# Sheet1.net
KiCad netlist of a schematic drawn in Altium Designer
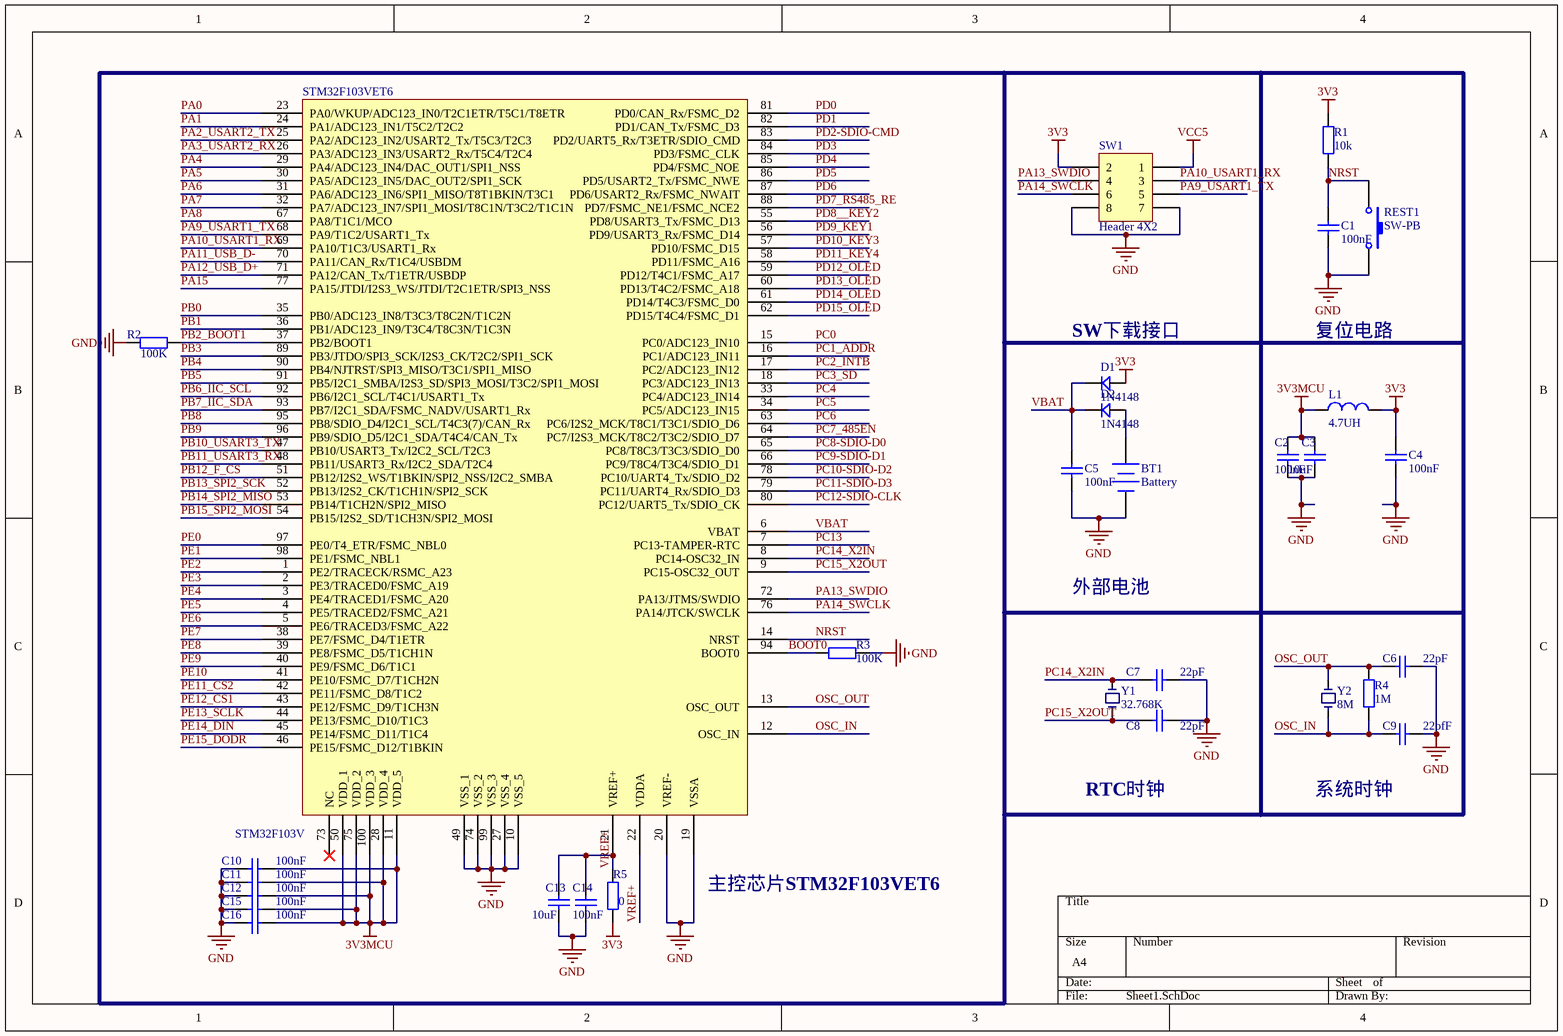
[diagram p0: Sheet1.SchDoc]

(export (version "E")
  (design (tool "Eeschema 10.0.6"))
  (components
    (comp (ref "BT1")
      (value "Battery")
      (footprint "BATTERY_CR1220")
      (description "备份电池")
      (fields (field (name "PUBLISHER") "Altium Limited"))
      (libsource (lib "liu_2016") (part "Battery"))
    )
    (comp (ref "C1")
      (value "100nF")
      (footprint "LC-0603_C")
      (description "无极性电容")
      (fields (field (name "PUBLISHER") "Altium Limited"))
      (libsource (lib "liu_2016") (part "Cap"))
    )
    (comp (ref "C2")
      (value "100nF")
      (footprint "LC-0603_C")
      (description "无极性电容")
      (fields (field (name "PUBLISHER") "Altium Limited"))
      (libsource (lib "liu_2016") (part "Cap"))
    )
    (comp (ref "C3")
      (value "10uF")
      (footprint "LC-0805_C")
      (description "贴片电容")
      (libsource (lib "Miscellaneous Devices LC") (part "0805 1.0pF (010) 0.25pF 50V"))
    )
    (comp (ref "C4")
      (value "100nF")
      (footprint "LC-0603_C")
      (description "无极性电容")
      (fields (field (name "PUBLISHER") "Altium Limited"))
      (libsource (lib "liu_2016") (part "Cap"))
    )
    (comp (ref "C5")
      (value "100nF")
      (footprint "LC-0603_C")
      (description "无极性电容")
      (fields (field (name "PUBLISHER") "Altium Limited"))
      (libsource (lib "liu_2016") (part "Cap"))
    )
    (comp (ref "C6")
      (value "22pF")
      (footprint "LC-0603_C")
      (description "无极性电容")
      (fields (field (name "PUBLISHER") "Altium Limited"))
      (libsource (lib "liu_2016") (part "Cap"))
    )
    (comp (ref "C7")
      (value "22pF")
      (footprint "LC-0603_C")
      (description "无极性电容")
      (fields (field (name "PUBLISHER") "Altium Limited"))
      (libsource (lib "liu_2016") (part "Cap"))
    )
    (comp (ref "C8")
      (value "22pF")
      (footprint "LC-0603_C")
      (description "无极性电容")
      (fields (field (name "PUBLISHER") "Altium Limited"))
      (libsource (lib "liu_2016") (part "Cap"))
    )
    (comp (ref "C9")
      (value "22pfF")
      (footprint "LC-0603_C")
      (description "无极性电容")
      (fields (field (name "PUBLISHER") "Altium Limited"))
      (libsource (lib "liu_2016") (part "Cap"))
    )
    (comp (ref "C10")
      (value "100nF")
      (footprint "LC-0603_C")
      (description "无极性电容")
      (fields (field (name "PUBLISHER") "Altium Limited"))
      (libsource (lib "liu_2016") (part "Cap"))
    )
    (comp (ref "C11")
      (value "100nF")
      (footprint "LC-0603_C")
      (description "无极性电容")
      (fields (field (name "PUBLISHER") "Altium Limited"))
      (libsource (lib "liu_2016") (part "Cap"))
    )
    (comp (ref "C12")
      (value "100nF")
      (footprint "LC-0603_C")
      (description "无极性电容")
      (fields (field (name "PUBLISHER") "Altium Limited"))
      (libsource (lib "liu_2016") (part "Cap"))
    )
    (comp (ref "C13")
      (value "10uF")
      (footprint "LC-0805_C")
      (description "贴片电容")
      (libsource (lib "Miscellaneous Devices LC") (part "0805 1.0pF (010) 0.25pF 50V"))
    )
    (comp (ref "C14")
      (value "100nF")
      (footprint "LC-0603_C")
      (description "无极性电容")
      (fields (field (name "PUBLISHER") "Altium Limited"))
      (libsource (lib "liu_2016") (part "Cap"))
    )
    (comp (ref "C15")
      (value "100nF")
      (footprint "LC-0603_C")
      (description "无极性电容")
      (fields (field (name "PUBLISHER") "Altium Limited"))
      (libsource (lib "liu_2016") (part "Cap"))
    )
    (comp (ref "C16")
      (value "100nF")
      (footprint "LC-0603_C")
      (description "无极性电容")
      (fields (field (name "PUBLISHER") "Altium Limited"))
      (libsource (lib "liu_2016") (part "Cap"))
    )
    (comp (ref "D1")
      (value "1N4148")
      (footprint "DIODE_SOP")
      (libsource (lib "Explorer STM32F407封装库") (part "D"))
    )
    (comp (ref "D2")
      (value "1N4148")
      (footprint "DIODE_SOP")
      (libsource (lib "Explorer STM32F407封装库") (part "D"))
    )
    (comp (ref "L1") (value "4.7UH") (footprint "LC-0805_L") (libsource (lib "liulei") (part "电感")))
    (comp (ref "R1")
      (value "10k")
      (footprint "LC-0603_R")
      (description "贴片电阻")
      (fields (field (name "PUBLISHER") "Altium Limited"))
      (libsource (lib "liu_2016") (part "Res1"))
    )
    (comp (ref "R2")
      (value "100K")
      (footprint "LC-0603_R")
      (description "贴片电阻")
      (fields (field (name "PUBLISHER") "Altium Limited"))
      (libsource (lib "") (part "Res1_2"))
    )
    (comp (ref "R3")
      (value "100K")
      (footprint "LC-0603_R")
      (description "贴片电阻")
      (fields (field (name "PUBLISHER") "Altium Limited"))
      (libsource (lib "") (part "Res1_2"))
    )
    (comp (ref "R4")
      (value "1M")
      (footprint "LC-0603_R")
      (description "贴片电阻")
      (fields (field (name "PUBLISHER") "Altium Limited"))
      (libsource (lib "") (part "Res1_1"))
    )
    (comp (ref "R5")
      (value "0")
      (footprint "LC-0603_R")
      (description "贴片电阻")
      (fields (field (name "PUBLISHER") "Altium Limited"))
      (libsource (lib "") (part "Res1_1"))
    )
    (comp (ref "REST1")
      (value "SW-PB")
      (footprint "SW-SMD1")
      (description "Switch")
      (fields (field (name "PUBLISHER") "Altium Limited"))
      (libsource (lib "PCB_Project") (part "SW-PB"))
    )
    (comp (ref "STM32F103VET6")
      (value "STM32F103V")
      (footprint "LQFP-100_M")
      (description "STM32单片机100引脚")
      (libsource (lib "liu_2016") (part "STM32F103V"))
    )
    (comp (ref "SW1")
      (value "Header 4X2")
      (footprint "HDR2X4")
      (description "Header, 4-Pin, Dual row")
      (fields (field (name "PUBLISHER") "Altium Limited"))
      (libsource (lib "Sparks") (part "Header 4X2"))
    )
    (comp (ref "Y1") (value "32.768K") (footprint "XTAL-长形 贴片") (libsource (lib "liulei") (part "晶振")))
    (comp (ref "Y2") (value "8M") (footprint "XTAL 直插") (libsource (lib "liulei") (part "晶振")))
  )
  (nets
    (net (code "1") (name "/BOOT0") (class "Default")
      (node (ref "R3") (pin "2") (pinfunction "2_2") (pintype "passive"))
      (node (ref "STM32F103VET6") (pin "94") (pinfunction "BOOT0_94") (pintype "passive"))
    )
    (net (code "2") (name "/NRST") (class "Default")
      (node (ref "C1") (pin "1") (pinfunction "1_1") (pintype "passive"))
      (node (ref "R1") (pin "2") (pinfunction "2_2") (pintype "passive"))
      (node (ref "REST1") (pin "1") (pinfunction "1_1") (pintype "passive"))
      (node (ref "STM32F103VET6") (pin "14") (pinfunction "NRST_14") (pintype "passive"))
    )
    (net (code "3") (name "/OSC_IN") (class "Default")
      (node (ref "C9") (pin "1") (pinfunction "1_1") (pintype "passive"))
      (node (ref "R4") (pin "1") (pinfunction "1_1") (pintype "passive"))
      (node (ref "STM32F103VET6") (pin "12") (pinfunction "OSC_IN_12") (pintype "passive"))
      (node (ref "Y2") (pin "1") (pinfunction "1_1") (pintype "passive"))
    )
    (net (code "4") (name "/OSC_OUT") (class "Default")
      (node (ref "C6") (pin "1") (pinfunction "1_1") (pintype "passive"))
      (node (ref "R4") (pin "2") (pinfunction "2_2") (pintype "passive"))
      (node (ref "STM32F103VET6") (pin "13") (pinfunction "OSC_OUT_13") (pintype "passive"))
      (node (ref "Y2") (pin "2") (pinfunction "2_2") (pintype "passive"))
    )
    (net (code "5") (name "/PA0") (class "Default")
      (node (ref "STM32F103VET6") (pin "23") (pinfunction "PA0/WKUP/ADC123_IN0/T2C1ETR/T5C1/T8ETR_23") (pintype "passive"))
    )
    (net (code "6") (name "/PA1") (class "Default")
      (node (ref "STM32F103VET6") (pin "24") (pinfunction "PA1/ADC123_IN1/T5C2/T2C2_24") (pintype "passive"))
    )
    (net (code "7") (name "/PA2_USART2_TX") (class "Default")
      (node (ref "STM32F103VET6") (pin "25") (pinfunction "PA2/ADC123_IN2/USART2_Tx/T5C3/T2C3_25") (pintype "passive"))
    )
    (net (code "8") (name "/PA3_USART2_RX") (class "Default")
      (node (ref "STM32F103VET6") (pin "26") (pinfunction "PA3/ADC123_IN3/USART2_Rx/T5C4/T2C4_26") (pintype "passive"))
    )
    (net (code "9") (name "/PA4") (class "Default")
      (node (ref "STM32F103VET6") (pin "29") (pinfunction "PA4/ADC123_IN4/DAC_OUT1/SPI1_NSS_29") (pintype "passive"))
    )
    (net (code "10") (name "/PA5") (class "Default")
      (node (ref "STM32F103VET6") (pin "30") (pinfunction "PA5/ADC123_IN5/DAC_OUT2/SPI1_SCK_30") (pintype "passive"))
    )
    (net (code "11") (name "/PA6") (class "Default")
      (node (ref "STM32F103VET6") (pin "31") (pinfunction "PA6/ADC123_IN6/SPI1_MISO/T8T1BKIN/T3C1_31") (pintype "passive"))
    )
    (net (code "12") (name "/PA7") (class "Default")
      (node (ref "STM32F103VET6") (pin "32") (pinfunction "PA7/ADC123_IN7/SPI1_MOSI/T8C1N/T3C2/T1C1N_32") (pintype "passive"))
    )
    (net (code "13") (name "/PA8") (class "Default")
      (node (ref "STM32F103VET6") (pin "67") (pinfunction "PA8/T1C1/MCO_67") (pintype "passive"))
    )
    (net (code "14") (name "/PA9_USART1_TX") (class "Default")
      (node (ref "STM32F103VET6") (pin "68") (pinfunction "PA9/T1C2/USART1_Tx_68") (pintype "passive"))
      (node (ref "SW1") (pin "5") (pinfunction "5_5") (pintype "passive"))
    )
    (net (code "15") (name "/PA10_USART1_RX") (class "Default")
      (node (ref "STM32F103VET6") (pin "69") (pinfunction "PA10/T1C3/USART1_Rx_69") (pintype "passive"))
      (node (ref "SW1") (pin "3") (pinfunction "3_3") (pintype "passive"))
    )
    (net (code "16") (name "/PA11_USB_D-") (class "Default")
      (node (ref "STM32F103VET6") (pin "70") (pinfunction "PA11/CAN_Rx/T1C4/USBDM_70") (pintype "passive"))
    )
    (net (code "17") (name "/PA12_USB_D+") (class "Default")
      (node (ref "STM32F103VET6") (pin "71") (pinfunction "PA12/CAN_Tx/T1ETR/USBDP_71") (pintype "passive"))
    )
    (net (code "18") (name "/PA13_SWDIO") (class "Default")
      (node (ref "STM32F103VET6") (pin "72") (pinfunction "PA13/JTMS/SWDIO_72") (pintype "passive"))
      (node (ref "SW1") (pin "4") (pinfunction "4_4") (pintype "passive"))
    )
    (net (code "19") (name "/PA14_SWCLK") (class "Default")
      (node (ref "STM32F103VET6") (pin "76") (pinfunction "PA14/JTCK/SWCLK_76") (pintype "passive"))
      (node (ref "SW1") (pin "6") (pinfunction "6_6") (pintype "passive"))
    )
    (net (code "20") (name "/PA15") (class "Default")
      (node (ref "STM32F103VET6") (pin "77") (pinfunction "PA15/JTDI/I2S3_WS/JTDI/T2C1ETR/SPI3_NSS_77") (pintype "passive"))
    )
    (net (code "21") (name "/PB0") (class "Default")
      (node (ref "STM32F103VET6") (pin "35") (pinfunction "PB0/ADC123_IN8/T3C3/T8C2N/T1C2N_35") (pintype "passive"))
    )
    (net (code "22") (name "/PB1") (class "Default")
      (node (ref "STM32F103VET6") (pin "36") (pinfunction "PB1/ADC123_IN9/T3C4/T8C3N/T1C3N_36") (pintype "passive"))
    )
    (net (code "23") (name "/PB2_BOOT1") (class "Default")
      (node (ref "R2") (pin "1") (pinfunction "1_1") (pintype "passive"))
      (node (ref "STM32F103VET6") (pin "37") (pinfunction "PB2/BOOT1_37") (pintype "passive"))
    )
    (net (code "24") (name "/PB3") (class "Default")
      (node (ref "STM32F103VET6") (pin "89") (pinfunction "PB3/JTDO/SPI3_SCK/I2S3_CK/T2C2/SPI1_SCK_89") (pintype "passive"))
    )
    (net (code "25") (name "/PB4") (class "Default")
      (node (ref "STM32F103VET6") (pin "90") (pinfunction "PB4/NJTRST/SPI3_MISO/T3C1/SPI1_MISO_90") (pintype "passive"))
    )
    (net (code "26") (name "/PB5") (class "Default")
      (node (ref "STM32F103VET6") (pin "91") (pinfunction "PB5/I2C1_SMBA/I2S3_SD/SPI3_MOSI/T3C2/SPI1_MOSI_91") (pintype "passive"))
    )
    (net (code "27") (name "/PB6_IIC_SCL") (class "Default")
      (node (ref "STM32F103VET6") (pin "92") (pinfunction "PB6/I2C1_SCL/T4C1/USART1_Tx_92") (pintype "passive"))
    )
    (net (code "28") (name "/PB7_IIC_SDA") (class "Default")
      (node (ref "STM32F103VET6") (pin "93") (pinfunction "PB7/I2C1_SDA/FSMC_NADV/USART1_Rx_93") (pintype "passive"))
    )
    (net (code "29") (name "/PB8") (class "Default")
      (node (ref "STM32F103VET6") (pin "95") (pinfunction "PB8/SDIO_D4/I2C1_SCL/T4C3(7)/CAN_Rx_95") (pintype "passive"))
    )
    (net (code "30") (name "/PB9") (class "Default")
      (node (ref "STM32F103VET6") (pin "96") (pinfunction "PB9/SDIO_D5/I2C1_SDA/T4C4/CAN_Tx_96") (pintype "passive"))
    )
    (net (code "31") (name "/PB10_USART3_TX") (class "Default")
      (node (ref "STM32F103VET6") (pin "47") (pinfunction "PB10/USART3_Tx/I2C2_SCL/T2C3_47") (pintype "passive"))
    )
    (net (code "32") (name "/PB11_USART3_RX") (class "Default")
      (node (ref "STM32F103VET6") (pin "48") (pinfunction "PB11/USART3_Rx/I2C2_SDA/T2C4_48") (pintype "passive"))
    )
    (net (code "33") (name "/PB12_F_CS") (class "Default")
      (node (ref "STM32F103VET6") (pin "51") (pinfunction "PB12/I2S2_WS/T1BKIN/SPI2_NSS/I2C2_SMBA_51") (pintype "passive"))
    )
    (net (code "34") (name "/PB13_SPI2_SCK") (class "Default")
      (node (ref "STM32F103VET6") (pin "52") (pinfunction "PB13/I2S2_CK/T1CH1N/SPI2_SCK_52") (pintype "passive"))
    )
    (net (code "35") (name "/PB14_SPI2_MISO") (class "Default")
      (node (ref "STM32F103VET6") (pin "53") (pinfunction "PB14/T1CH2N/SPI2_MISO_53") (pintype "passive"))
    )
    (net (code "36") (name "/PB15_SPI2_MOSI") (class "Default")
      (node (ref "STM32F103VET6") (pin "54") (pinfunction "PB15/I2S2_SD/T1CH3N/SPI2_MOSI_54") (pintype "passive"))
    )
    (net (code "37") (name "/PC0") (class "Default")
      (node (ref "STM32F103VET6") (pin "15") (pinfunction "PC0/ADC123_IN10_15") (pintype "passive"))
    )
    (net (code "38") (name "/PC1_ADDR") (class "Default")
      (node (ref "STM32F103VET6") (pin "16") (pinfunction "PC1/ADC123_IN11_16") (pintype "passive"))
    )
    (net (code "39") (name "/PC2_INTB") (class "Default")
      (node (ref "STM32F103VET6") (pin "17") (pinfunction "PC2/ADC123_IN12_17") (pintype "passive"))
    )
    (net (code "40") (name "/PC3_SD") (class "Default")
      (node (ref "STM32F103VET6") (pin "18") (pinfunction "PC3/ADC123_IN13_18") (pintype "passive"))
    )
    (net (code "41") (name "/PC4") (class "Default")
      (node (ref "STM32F103VET6") (pin "33") (pinfunction "PC4/ADC123_IN14_33") (pintype "passive"))
    )
    (net (code "42") (name "/PC5") (class "Default")
      (node (ref "STM32F103VET6") (pin "34") (pinfunction "PC5/ADC123_IN15_34") (pintype "passive"))
    )
    (net (code "43") (name "/PC6") (class "Default")
      (node (ref "STM32F103VET6") (pin "63") (pinfunction "PC6/I2S2_MCK/T8C1/T3C1/SDIO_D6_63") (pintype "passive"))
    )
    (net (code "44") (name "/PC7_485EN") (class "Default")
      (node (ref "STM32F103VET6") (pin "64") (pinfunction "PC7/I2S3_MCK/T8C2/T3C2/SDIO_D7_64") (pintype "passive"))
    )
    (net (code "45") (name "/PC8-SDIO-D0") (class "Default")
      (node (ref "STM32F103VET6") (pin "65") (pinfunction "PC8/T8C3/T3C3/SDIO_D0_65") (pintype "passive"))
    )
    (net (code "46") (name "/PC9-SDIO-D1") (class "Default")
      (node (ref "STM32F103VET6") (pin "66") (pinfunction "PC9/T8C4/T3C4/SDIO_D1_66") (pintype "passive"))
    )
    (net (code "47") (name "/PC10-SDIO-D2") (class "Default")
      (node (ref "STM32F103VET6") (pin "78") (pinfunction "PC10/UART4_Tx/SDIO_D2_78") (pintype "passive"))
    )
    (net (code "48") (name "/PC11-SDIO-D3") (class "Default")
      (node (ref "STM32F103VET6") (pin "79") (pinfunction "PC11/UART4_Rx/SDIO_D3_79") (pintype "passive"))
    )
    (net (code "49") (name "/PC12-SDIO-CLK") (class "Default")
      (node (ref "STM32F103VET6") (pin "80") (pinfunction "PC12/UART5_Tx/SDIO_CK_80") (pintype "passive"))
    )
    (net (code "50") (name "/PC13") (class "Default")
      (node (ref "STM32F103VET6") (pin "7") (pinfunction "PC13-TAMPER-RTC_7") (pintype "passive"))
    )
    (net (code "51") (name "/PC14_X2IN") (class "Default")
      (node (ref "C7") (pin "1") (pinfunction "1_1") (pintype "passive"))
      (node (ref "STM32F103VET6") (pin "8") (pinfunction "PC14-OSC32_IN_8") (pintype "passive"))
      (node (ref "Y1") (pin "2") (pinfunction "2_2") (pintype "passive"))
    )
    (net (code "52") (name "/PC15_X2OUT") (class "Default")
      (node (ref "C8") (pin "1") (pinfunction "1_1") (pintype "passive"))
      (node (ref "STM32F103VET6") (pin "9") (pinfunction "PC15-OSC32_OUT_9") (pintype "passive"))
      (node (ref "Y1") (pin "1") (pinfunction "1_1") (pintype "passive"))
    )
    (net (code "53") (name "/PD0") (class "Default")
      (node (ref "STM32F103VET6") (pin "81") (pinfunction "PD0/CAN_Rx/FSMC_D2_81") (pintype "passive"))
    )
    (net (code "54") (name "/PD1") (class "Default")
      (node (ref "STM32F103VET6") (pin "82") (pinfunction "PD1/CAN_Tx/FSMC_D3_82") (pintype "passive"))
    )
    (net (code "55") (name "/PD2-SDIO-CMD") (class "Default")
      (node (ref "STM32F103VET6") (pin "83") (pinfunction "PD2/UART5_Rx/T3ETR/SDIO_CMD_83") (pintype "passive"))
    )
    (net (code "56") (name "/PD3") (class "Default")
      (node (ref "STM32F103VET6") (pin "84") (pinfunction "PD3/FSMC_CLK_84") (pintype "passive"))
    )
    (net (code "57") (name "/PD4") (class "Default")
      (node (ref "STM32F103VET6") (pin "85") (pinfunction "PD4/FSMC_NOE_85") (pintype "passive"))
    )
    (net (code "58") (name "/PD5") (class "Default")
      (node (ref "STM32F103VET6") (pin "86") (pinfunction "PD5/USART2_Tx/FSMC_NWE_86") (pintype "passive"))
    )
    (net (code "59") (name "/PD6") (class "Default")
      (node (ref "STM32F103VET6") (pin "87") (pinfunction "PD6/USART2_Rx/FSMC_NWAIT_87") (pintype "passive"))
    )
    (net (code "60") (name "/PD7_RS485_RE") (class "Default")
      (node (ref "STM32F103VET6") (pin "88") (pinfunction "PD7/FSMC_NE1/FSMC_NCE2_88") (pintype "passive"))
    )
    (net (code "61") (name "/PD8__KEY2") (class "Default")
      (node (ref "STM32F103VET6") (pin "55") (pinfunction "PD8/USART3_Tx/FSMC_D13_55") (pintype "passive"))
    )
    (net (code "62") (name "/PD9_KEY1") (class "Default")
      (node (ref "STM32F103VET6") (pin "56") (pinfunction "PD9/USART3_Rx/FSMC_D14_56") (pintype "passive"))
    )
    (net (code "63") (name "/PD10_KEY3") (class "Default")
      (node (ref "STM32F103VET6") (pin "57") (pinfunction "PD10/FSMC_D15_57") (pintype "passive"))
    )
    (net (code "64") (name "/PD11_KEY4") (class "Default")
      (node (ref "STM32F103VET6") (pin "58") (pinfunction "PD11/FSMC_A16_58") (pintype "passive"))
    )
    (net (code "65") (name "/PD12_OLED") (class "Default")
      (node (ref "STM32F103VET6") (pin "59") (pinfunction "PD12/T4C1/FSMC_A17_59") (pintype "passive"))
    )
    (net (code "66") (name "/PD13_OLED") (class "Default")
      (node (ref "STM32F103VET6") (pin "60") (pinfunction "PD13/T4C2/FSMC_A18_60") (pintype "passive"))
    )
    (net (code "67") (name "/PD14_OLED") (class "Default")
      (node (ref "STM32F103VET6") (pin "61") (pinfunction "PD14/T4C3/FSMC_D0_61") (pintype "passive"))
    )
    (net (code "68") (name "/PD15_OLED") (class "Default")
      (node (ref "STM32F103VET6") (pin "62") (pinfunction "PD15/T4C4/FSMC_D1_62") (pintype "passive"))
    )
    (net (code "69") (name "/PE0") (class "Default")
      (node (ref "STM32F103VET6") (pin "97") (pinfunction "PE0/T4_ETR/FSMC_NBL0_97") (pintype "passive"))
    )
    (net (code "70") (name "/PE1") (class "Default")
      (node (ref "STM32F103VET6") (pin "98") (pinfunction "PE1/FSMC_NBL1_98") (pintype "passive"))
    )
    (net (code "71") (name "/PE2") (class "Default")
      (node (ref "STM32F103VET6") (pin "1") (pinfunction "PE2/TRACECK/RSMC_A23_1") (pintype "passive"))
    )
    (net (code "72") (name "/PE3") (class "Default")
      (node (ref "STM32F103VET6") (pin "2") (pinfunction "PE3/TRACED0/FSMC_A19_2") (pintype "passive"))
    )
    (net (code "73") (name "/PE4") (class "Default")
      (node (ref "STM32F103VET6") (pin "3") (pinfunction "PE4/TRACED1/FSMC_A20_3") (pintype "passive"))
    )
    (net (code "74") (name "/PE5") (class "Default")
      (node (ref "STM32F103VET6") (pin "4") (pinfunction "PE5/TRACED2/FSMC_A21_4") (pintype "passive"))
    )
    (net (code "75") (name "/PE6") (class "Default")
      (node (ref "STM32F103VET6") (pin "5") (pinfunction "PE6/TRACED3/FSMC_A22_5") (pintype "passive"))
    )
    (net (code "76") (name "/PE7") (class "Default")
      (node (ref "STM32F103VET6") (pin "38") (pinfunction "PE7/FSMC_D4/T1ETR_38") (pintype "passive"))
    )
    (net (code "77") (name "/PE8") (class "Default")
      (node (ref "STM32F103VET6") (pin "39") (pinfunction "PE8/FSMC_D5/T1CH1N_39") (pintype "passive"))
    )
    (net (code "78") (name "/PE9") (class "Default")
      (node (ref "STM32F103VET6") (pin "40") (pinfunction "PE9/FSMC_D6/T1C1_40") (pintype "passive"))
    )
    (net (code "79") (name "/PE10") (class "Default")
      (node (ref "STM32F103VET6") (pin "41") (pinfunction "PE10/FSMC_D7/T1CH2N_41") (pintype "passive"))
    )
    (net (code "80") (name "/PE11_CS2") (class "Default")
      (node (ref "STM32F103VET6") (pin "42") (pinfunction "PE11/FSMC_D8/T1C2_42") (pintype "passive"))
    )
    (net (code "81") (name "/PE12_CS1") (class "Default")
      (node (ref "STM32F103VET6") (pin "43") (pinfunction "PE12/FSMC_D9/T1CH3N_43") (pintype "passive"))
    )
    (net (code "82") (name "/PE13_SCLK") (class "Default")
      (node (ref "STM32F103VET6") (pin "44") (pinfunction "PE13/FSMC_D10/T1C3_44") (pintype "passive"))
    )
    (net (code "83") (name "/PE14_DIN") (class "Default")
      (node (ref "STM32F103VET6") (pin "45") (pinfunction "PE14/FSMC_D11/T1C4_45") (pintype "passive"))
    )
    (net (code "84") (name "/PE15_DODR") (class "Default")
      (node (ref "STM32F103VET6") (pin "46") (pinfunction "PE15/FSMC_D12/T1BKIN_46") (pintype "passive"))
    )
    (net (code "85") (name "/VBAT") (class "Default")
      (node (ref "C5") (pin "2") (pinfunction "2_2") (pintype "passive"))
      (node (ref "D1") (pin "2") (pintype "passive"))
      (node (ref "D2") (pin "2") (pintype "passive"))
      (node (ref "STM32F103VET6") (pin "6") (pinfunction "VBAT_6") (pintype "passive"))
    )
    (net (code "86") (name "/VREF+") (class "Default")
      (node (ref "C13") (pin "2") (pinfunction "2_2") (pintype "passive"))
      (node (ref "C14") (pin "2") (pinfunction "2_2") (pintype "passive"))
      (node (ref "R5") (pin "2") (pinfunction "2_2") (pintype "passive"))
      (node (ref "STM32F103VET6") (pin "21") (pinfunction "VREF+_21") (pintype "passive"))
      (node (ref "STM32F103VET6") (pin "22") (pinfunction "VDDA_22") (pintype "passive"))
    )
    (net (code "87") (name "3V3") (class "Default")
      (node (ref "C4") (pin "2") (pinfunction "2_2") (pintype "passive"))
      (node (ref "D1") (pin "1") (pintype "passive"))
      (node (ref "L1") (pin "2") (pinfunction "2_2") (pintype "passive"))
      (node (ref "R1") (pin "1") (pinfunction "1_1") (pintype "passive"))
      (node (ref "R5") (pin "1") (pinfunction "1_1") (pintype "passive"))
      (node (ref "SW1") (pin "2") (pinfunction "2_2") (pintype "passive"))
    )
    (net (code "88") (name "3V3MCU") (class "Default")
      (node (ref "C10") (pin "2") (pinfunction "2_2") (pintype "passive"))
      (node (ref "C11") (pin "2") (pinfunction "2_2") (pintype "passive"))
      (node (ref "C12") (pin "2") (pinfunction "2_2") (pintype "passive"))
      (node (ref "C15") (pin "2") (pinfunction "2_2") (pintype "passive"))
      (node (ref "C16") (pin "2") (pinfunction "2_2") (pintype "passive"))
      (node (ref "C2") (pin "2") (pinfunction "2_2") (pintype "passive"))
      (node (ref "C3") (pin "2") (pinfunction "2_2") (pintype "passive"))
      (node (ref "L1") (pin "1") (pinfunction "1_1") (pintype "passive"))
      (node (ref "STM32F103VET6") (pin "100") (pinfunction "VDD_3_100") (pintype "passive"))
      (node (ref "STM32F103VET6") (pin "11") (pinfunction "VDD_5_11") (pintype "passive"))
      (node (ref "STM32F103VET6") (pin "28") (pinfunction "VDD_4_28") (pintype "passive"))
      (node (ref "STM32F103VET6") (pin "50") (pinfunction "VDD_1_50") (pintype "passive"))
      (node (ref "STM32F103VET6") (pin "75") (pinfunction "VDD_2_75") (pintype "passive"))
    )
    (net (code "89") (name "GND") (class "Default")
      (node (ref "BT1") (pin "2") (pinfunction "-_2") (pintype "passive"))
      (node (ref "C1") (pin "2") (pinfunction "2_2") (pintype "passive"))
      (node (ref "C10") (pin "1") (pinfunction "1_1") (pintype "passive"))
      (node (ref "C11") (pin "1") (pinfunction "1_1") (pintype "passive"))
      (node (ref "C12") (pin "1") (pinfunction "1_1") (pintype "passive"))
      (node (ref "C13") (pin "1") (pinfunction "1_1") (pintype "passive"))
      (node (ref "C14") (pin "1") (pinfunction "1_1") (pintype "passive"))
      (node (ref "C15") (pin "1") (pinfunction "1_1") (pintype "passive"))
      (node (ref "C16") (pin "1") (pinfunction "1_1") (pintype "passive"))
      (node (ref "C2") (pin "1") (pinfunction "1_1") (pintype "passive"))
      (node (ref "C3") (pin "1") (pinfunction "1_1") (pintype "passive"))
      (node (ref "C4") (pin "1") (pinfunction "1_1") (pintype "passive"))
      (node (ref "C5") (pin "1") (pinfunction "1_1") (pintype "passive"))
      (node (ref "C6") (pin "2") (pinfunction "2_2") (pintype "passive"))
      (node (ref "C7") (pin "2") (pinfunction "2_2") (pintype "passive"))
      (node (ref "C8") (pin "2") (pinfunction "2_2") (pintype "passive"))
      (node (ref "C9") (pin "2") (pinfunction "2_2") (pintype "passive"))
      (node (ref "R2") (pin "2") (pinfunction "2_2") (pintype "passive"))
      (node (ref "R3") (pin "1") (pinfunction "1_1") (pintype "passive"))
      (node (ref "REST1") (pin "2") (pinfunction "2_2") (pintype "passive"))
      (node (ref "STM32F103VET6") (pin "10") (pinfunction "VSS_5_10") (pintype "passive"))
      (node (ref "STM32F103VET6") (pin "19") (pinfunction "VSSA_19") (pintype "passive"))
      (node (ref "STM32F103VET6") (pin "20") (pinfunction "VREF-_20") (pintype "passive"))
      (node (ref "STM32F103VET6") (pin "27") (pinfunction "VSS_4_27") (pintype "passive"))
      (node (ref "STM32F103VET6") (pin "49") (pinfunction "VSS_1_49") (pintype "passive"))
      (node (ref "STM32F103VET6") (pin "74") (pinfunction "VSS_2_74") (pintype "passive"))
      (node (ref "STM32F103VET6") (pin "99") (pinfunction "VSS_3_99") (pintype "passive"))
      (node (ref "SW1") (pin "7") (pinfunction "7_7") (pintype "passive"))
      (node (ref "SW1") (pin "8") (pinfunction "8_8") (pintype "passive"))
    )
    (net (code "90") (name "Net-(BT1-+)") (class "Default")
      (node (ref "BT1") (pin "1") (pinfunction "+_1") (pintype "passive"))
      (node (ref "D2") (pin "1") (pintype "passive"))
    )
    (net (code "91") (name "VCC5") (class "Default")
      (node (ref "SW1") (pin "1") (pinfunction "1_1") (pintype "passive"))
    )
    (net (code "92") (name "unconnected-(STM32F103VET6-NC-Pad73)") (class "Default")
      (node (ref "STM32F103VET6") (pin "73") (pinfunction "NC_73") (pintype "passive+no_connect"))
    )
  )
)
